# Body-Shield.net
KiCad netlist of a schematic drawn in EAGLE
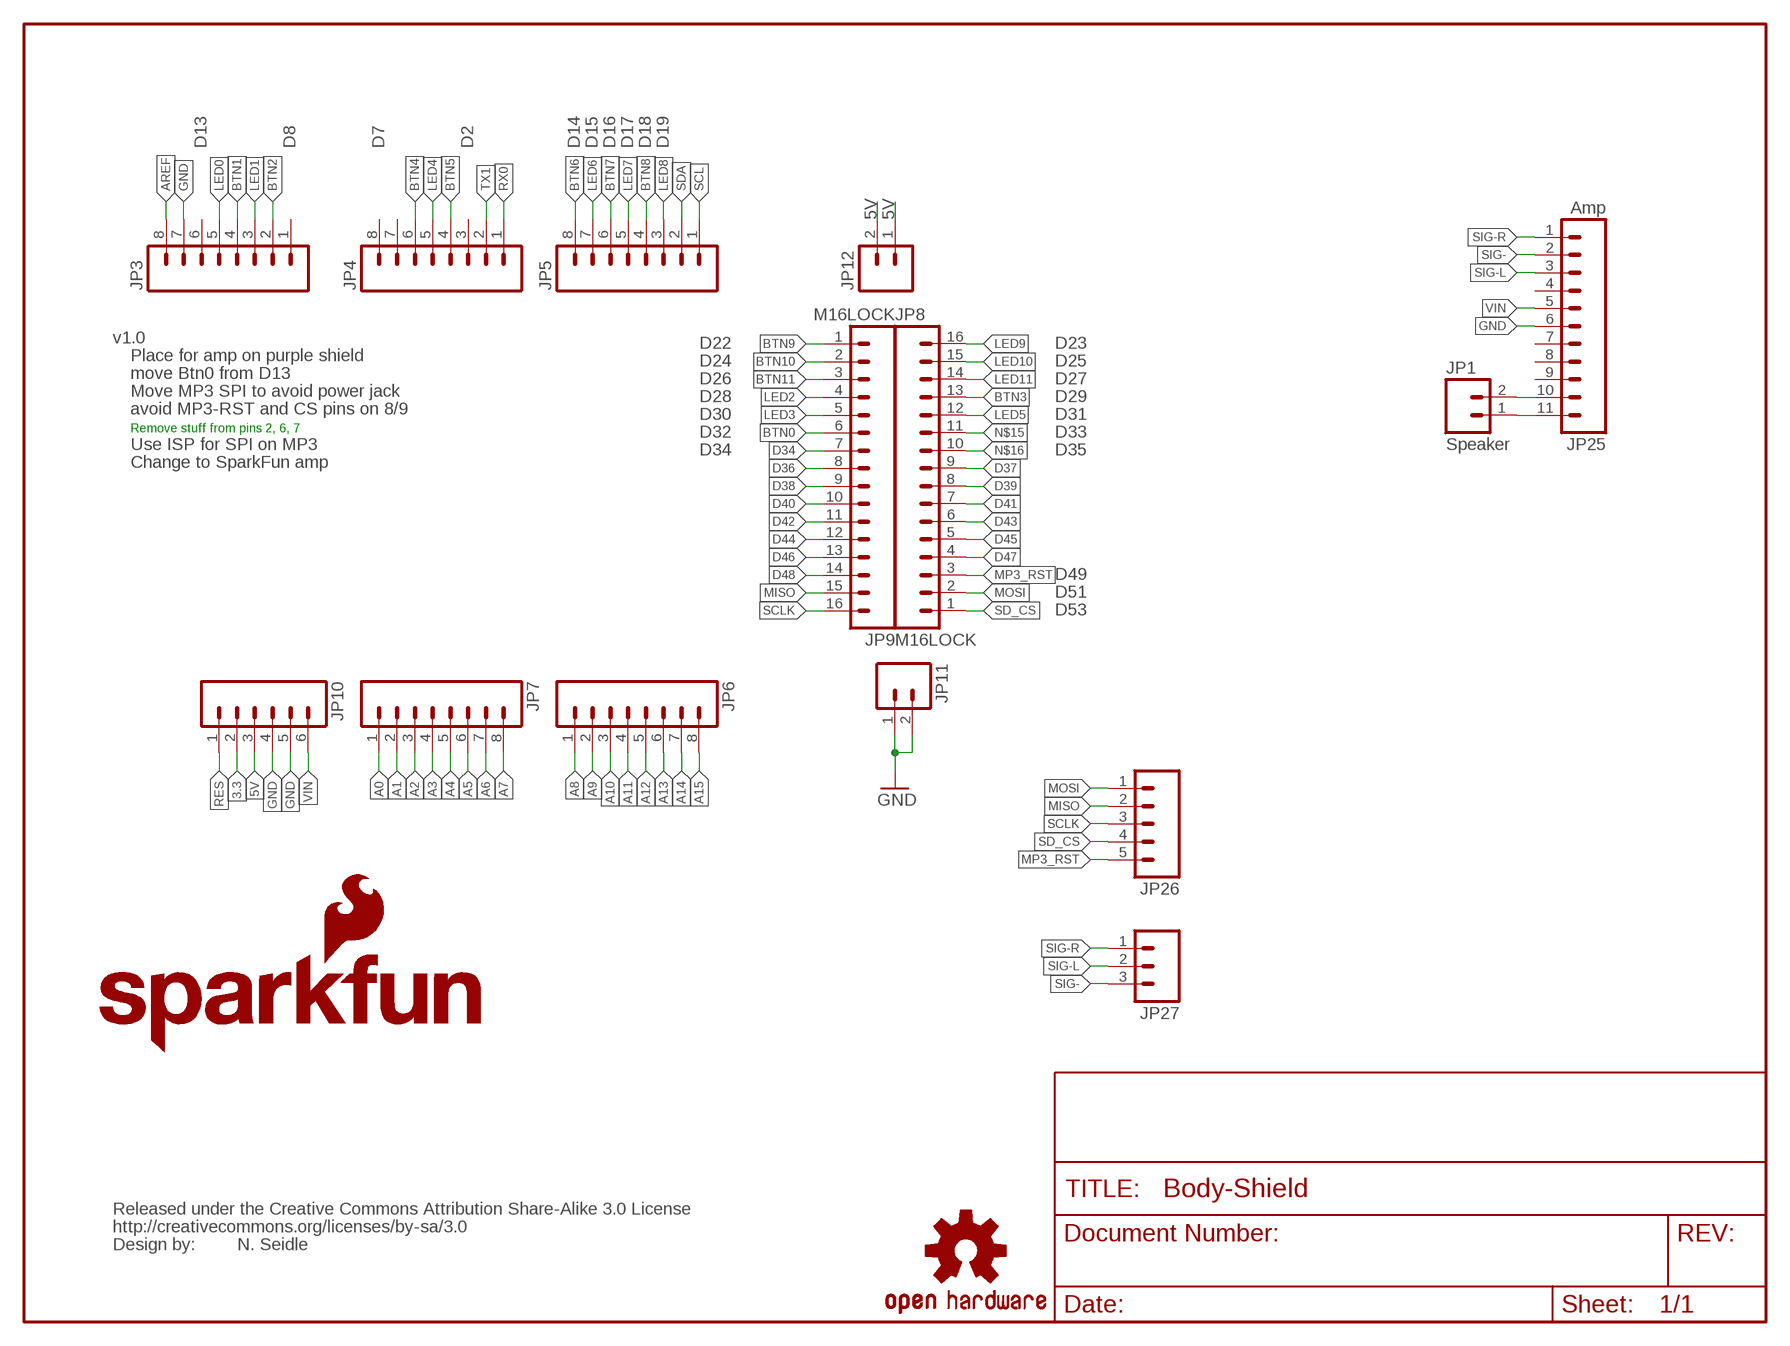
[diagram p0: schematic, sheet 1, part 1 of 2]
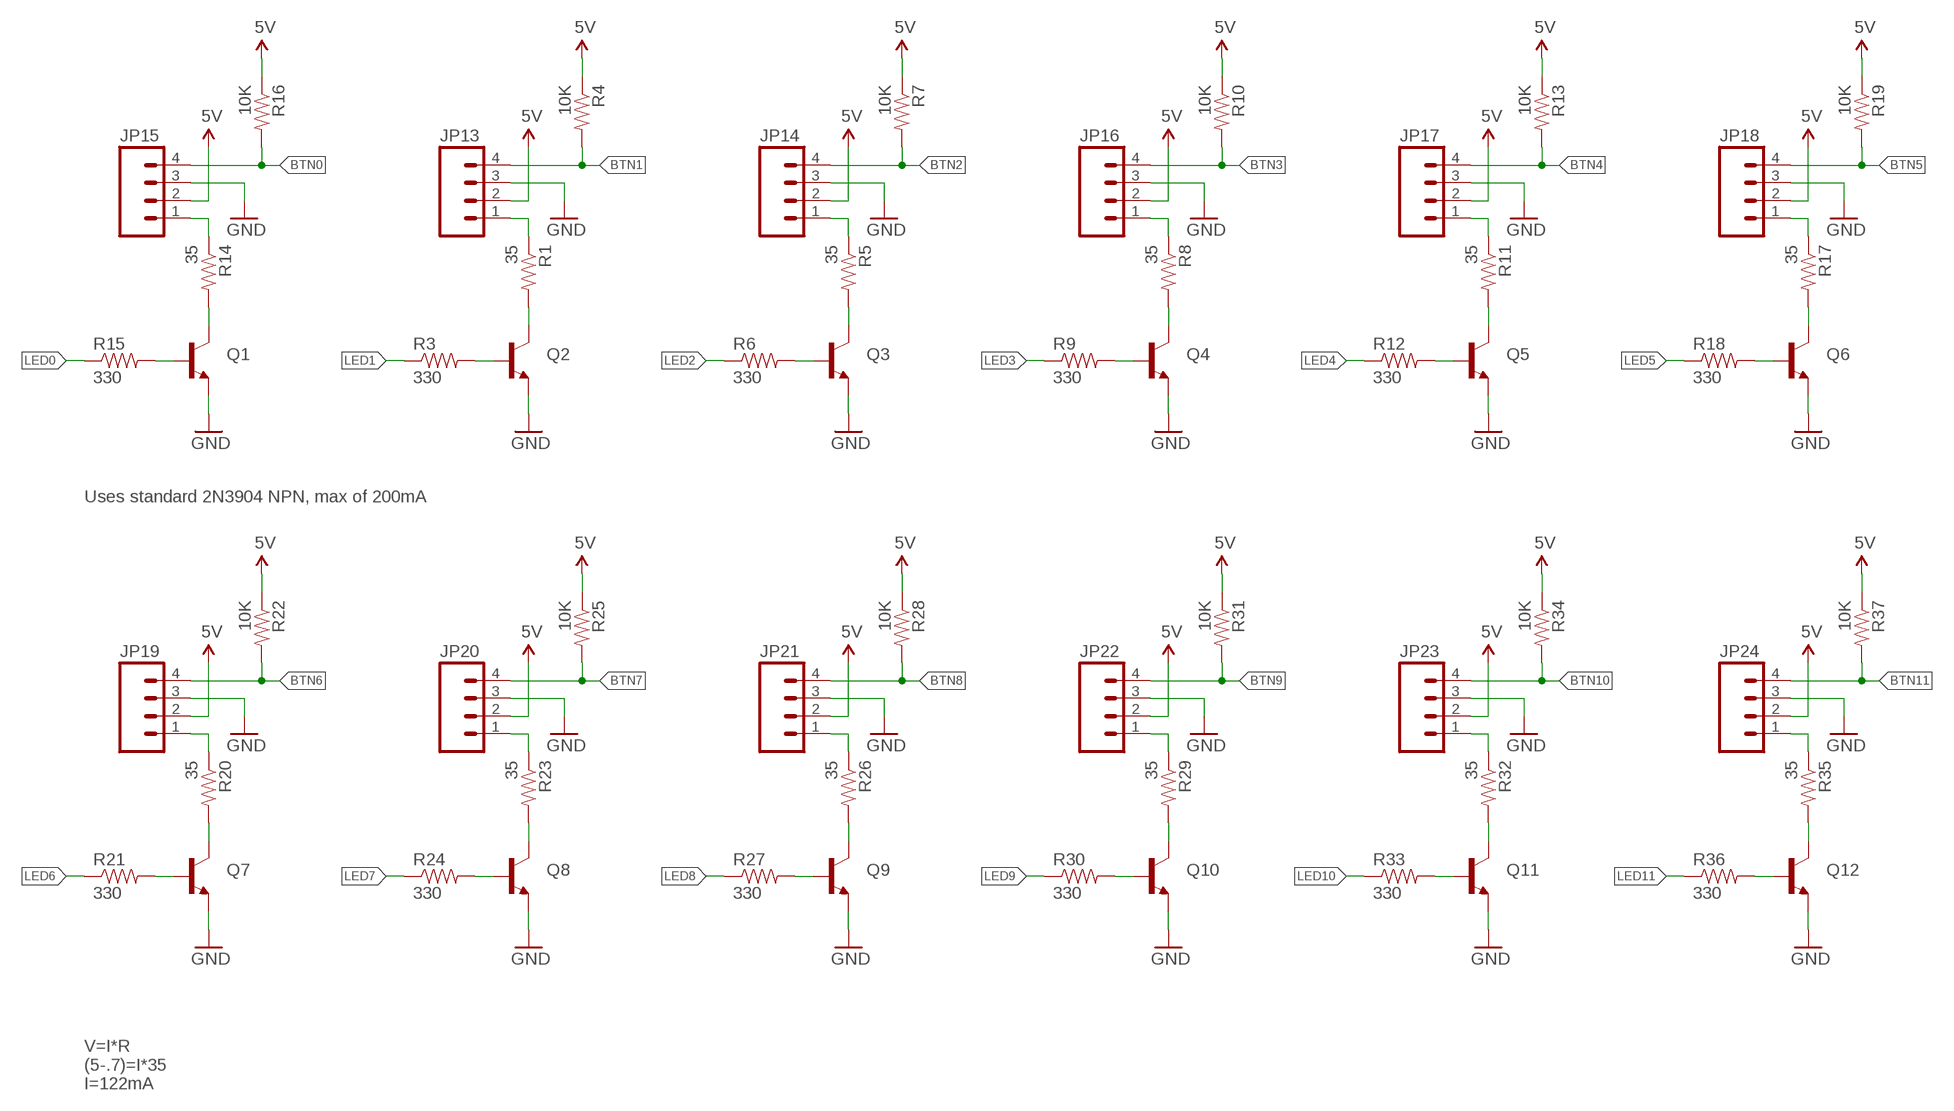
[diagram p1: schematic, sheet 1, part 2 of 2]

(export (version "E")
  (design (tool "Eeschema 10.0.6"))
  (components
    (comp (ref "JP1")
      (value "Speaker")
      (footprint "eagle-import:JST-2-PTH-VERT")
      (libsource (lib "eagle-import") (part "M02JST-PTH-VERT"))
    )
    (comp (ref "JP3")
      (value "M08LOCK")
      (footprint "eagle-import:1X08_LOCK")
      (libsource (lib "eagle-import") (part "M08LOCK"))
    )
    (comp (ref "JP4")
      (value "M08LOCK")
      (footprint "eagle-import:1X08_LOCK")
      (libsource (lib "eagle-import") (part "M08LOCK"))
    )
    (comp (ref "JP5")
      (value "M08LOCK")
      (footprint "eagle-import:1X08_LOCK")
      (libsource (lib "eagle-import") (part "M08LOCK"))
    )
    (comp (ref "JP6")
      (value "M08LOCK")
      (footprint "eagle-import:1X08_LOCK")
      (libsource (lib "eagle-import") (part "M08LOCK"))
    )
    (comp (ref "JP7")
      (value "M08LOCK")
      (footprint "eagle-import:1X08_LOCK")
      (libsource (lib "eagle-import") (part "M08LOCK"))
    )
    (comp (ref "JP8")
      (value "M16LOCK")
      (footprint "eagle-import:1X16_LOCK")
      (libsource (lib "eagle-import") (part "M16LOCK"))
    )
    (comp (ref "JP9")
      (value "M16LOCK")
      (footprint "eagle-import:1X16_LOCK")
      (libsource (lib "eagle-import") (part "M16LOCK"))
    )
    (comp (ref "JP10")
      (value "M06LOCK")
      (footprint "eagle-import:1X06_LOCK")
      (libsource (lib "eagle-import") (part "M06LOCK"))
    )
    (comp (ref "JP11")
      (value "M02LOCK")
      (footprint "eagle-import:1X02_LOCK")
      (libsource (lib "eagle-import") (part "M02LOCK"))
    )
    (comp (ref "JP12")
      (value "M02LOCK")
      (footprint "eagle-import:1X02_LOCK")
      (libsource (lib "eagle-import") (part "M02LOCK"))
    )
    (comp (ref "JP13")
      (value "M04JST-PTH-VERT")
      (footprint "eagle-import:JST-4-PTH-VERT")
      (libsource (lib "eagle-import") (part "M04JST-PTH-VERT"))
    )
    (comp (ref "JP14")
      (value "M04JST-PTH-VERT")
      (footprint "eagle-import:JST-4-PTH-VERT")
      (libsource (lib "eagle-import") (part "M04JST-PTH-VERT"))
    )
    (comp (ref "JP15")
      (value "M04JST-PTH-VERT")
      (footprint "eagle-import:JST-4-PTH-VERT")
      (libsource (lib "eagle-import") (part "M04JST-PTH-VERT"))
    )
    (comp (ref "JP16")
      (value "M04JST-PTH-VERT")
      (footprint "eagle-import:JST-4-PTH-VERT")
      (libsource (lib "eagle-import") (part "M04JST-PTH-VERT"))
    )
    (comp (ref "JP17")
      (value "M04JST-PTH-VERT")
      (footprint "eagle-import:JST-4-PTH-VERT")
      (libsource (lib "eagle-import") (part "M04JST-PTH-VERT"))
    )
    (comp (ref "JP18")
      (value "M04JST-PTH-VERT")
      (footprint "eagle-import:JST-4-PTH-VERT")
      (libsource (lib "eagle-import") (part "M04JST-PTH-VERT"))
    )
    (comp (ref "JP19")
      (value "M04JST-PTH-VERT")
      (footprint "eagle-import:JST-4-PTH-VERT")
      (libsource (lib "eagle-import") (part "M04JST-PTH-VERT"))
    )
    (comp (ref "JP20")
      (value "M04JST-PTH-VERT")
      (footprint "eagle-import:JST-4-PTH-VERT")
      (libsource (lib "eagle-import") (part "M04JST-PTH-VERT"))
    )
    (comp (ref "JP21")
      (value "M04JST-PTH-VERT")
      (footprint "eagle-import:JST-4-PTH-VERT")
      (libsource (lib "eagle-import") (part "M04JST-PTH-VERT"))
    )
    (comp (ref "JP22")
      (value "M04JST-PTH-VERT")
      (footprint "eagle-import:JST-4-PTH-VERT")
      (libsource (lib "eagle-import") (part "M04JST-PTH-VERT"))
    )
    (comp (ref "JP23")
      (value "M04JST-PTH-VERT")
      (footprint "eagle-import:JST-4-PTH-VERT")
      (libsource (lib "eagle-import") (part "M04JST-PTH-VERT"))
    )
    (comp (ref "JP24")
      (value "M04JST-PTH-VERT")
      (footprint "eagle-import:JST-4-PTH-VERT")
      (libsource (lib "eagle-import") (part "M04JST-PTH-VERT"))
    )
    (comp (ref "JP25")
      (value "Amp")
      (footprint "eagle-import:1X11")
      (libsource (lib "eagle-import") (part "M11PTH"))
    )
    (comp (ref "JP26")
      (value "M05JST")
      (footprint "eagle-import:JST-5-PTH")
      (libsource (lib "eagle-import") (part "M05JST"))
    )
    (comp (ref "JP27")
      (value "M03JST-PTH")
      (footprint "eagle-import:JST-3-PTH")
      (libsource (lib "eagle-import") (part "M03JST-PTH"))
    )
    (comp (ref "LOGO1")
      (value "SFE_LOGO_NAME_FLAME.1_INCH")
      (footprint "eagle-import:SFE_LOGO_NAME_FLAME_.1")
      (libsource (lib "eagle-import") (part "SFE_LOGO_NAME_FLAME.1_INCH"))
    )
    (comp (ref "LOGO2")
      (value "OSHW-LOGOS")
      (footprint "eagle-import:OSHW-LOGO-S")
      (libsource (lib "eagle-import") (part "OSHW-LOGOS"))
    )
    (comp (ref "Q1")
      (value "TRANSISTOR_NPN2N3904")
      (footprint "eagle-import:TO-92")
      (libsource (lib "eagle-import") (part "TRANSISTOR_NPN2N3904"))
    )
    (comp (ref "Q2")
      (value "TRANSISTOR_NPN2N3904")
      (footprint "eagle-import:TO-92")
      (libsource (lib "eagle-import") (part "TRANSISTOR_NPN2N3904"))
    )
    (comp (ref "Q3")
      (value "TRANSISTOR_NPN2N3904")
      (footprint "eagle-import:TO-92")
      (libsource (lib "eagle-import") (part "TRANSISTOR_NPN2N3904"))
    )
    (comp (ref "Q4")
      (value "TRANSISTOR_NPN2N3904")
      (footprint "eagle-import:TO-92")
      (libsource (lib "eagle-import") (part "TRANSISTOR_NPN2N3904"))
    )
    (comp (ref "Q5")
      (value "TRANSISTOR_NPN2N3904")
      (footprint "eagle-import:TO-92")
      (libsource (lib "eagle-import") (part "TRANSISTOR_NPN2N3904"))
    )
    (comp (ref "Q6")
      (value "TRANSISTOR_NPN2N3904")
      (footprint "eagle-import:TO-92")
      (libsource (lib "eagle-import") (part "TRANSISTOR_NPN2N3904"))
    )
    (comp (ref "Q7")
      (value "TRANSISTOR_NPN2N3904")
      (footprint "eagle-import:TO-92")
      (libsource (lib "eagle-import") (part "TRANSISTOR_NPN2N3904"))
    )
    (comp (ref "Q8")
      (value "TRANSISTOR_NPN2N3904")
      (footprint "eagle-import:TO-92")
      (libsource (lib "eagle-import") (part "TRANSISTOR_NPN2N3904"))
    )
    (comp (ref "Q9")
      (value "TRANSISTOR_NPN2N3904")
      (footprint "eagle-import:TO-92")
      (libsource (lib "eagle-import") (part "TRANSISTOR_NPN2N3904"))
    )
    (comp (ref "Q10")
      (value "TRANSISTOR_NPN2N3904")
      (footprint "eagle-import:TO-92")
      (libsource (lib "eagle-import") (part "TRANSISTOR_NPN2N3904"))
    )
    (comp (ref "Q11")
      (value "TRANSISTOR_NPN2N3904")
      (footprint "eagle-import:TO-92")
      (libsource (lib "eagle-import") (part "TRANSISTOR_NPN2N3904"))
    )
    (comp (ref "Q12")
      (value "TRANSISTOR_NPN2N3904")
      (footprint "eagle-import:TO-92")
      (libsource (lib "eagle-import") (part "TRANSISTOR_NPN2N3904"))
    )
    (comp (ref "R1")
      (value "35")
      (footprint "eagle-import:AXIAL-0.3")
      (libsource (lib "eagle-import") (part "RESISTORPTH1"))
    )
    (comp (ref "R3")
      (value "330")
      (footprint "eagle-import:AXIAL-0.3")
      (libsource (lib "eagle-import") (part "RESISTORPTH1"))
    )
    (comp (ref "R4")
      (value "10K")
      (footprint "eagle-import:AXIAL-0.3")
      (libsource (lib "eagle-import") (part "RESISTORPTH1"))
    )
    (comp (ref "R5")
      (value "35")
      (footprint "eagle-import:AXIAL-0.3")
      (libsource (lib "eagle-import") (part "RESISTORPTH1"))
    )
    (comp (ref "R6")
      (value "330")
      (footprint "eagle-import:AXIAL-0.3")
      (libsource (lib "eagle-import") (part "RESISTORPTH1"))
    )
    (comp (ref "R7")
      (value "10K")
      (footprint "eagle-import:AXIAL-0.3")
      (libsource (lib "eagle-import") (part "RESISTORPTH1"))
    )
    (comp (ref "R8")
      (value "35")
      (footprint "eagle-import:AXIAL-0.3")
      (libsource (lib "eagle-import") (part "RESISTORPTH1"))
    )
    (comp (ref "R9")
      (value "330")
      (footprint "eagle-import:AXIAL-0.3")
      (libsource (lib "eagle-import") (part "RESISTORPTH1"))
    )
    (comp (ref "R10")
      (value "10K")
      (footprint "eagle-import:AXIAL-0.3")
      (libsource (lib "eagle-import") (part "RESISTORPTH1"))
    )
    (comp (ref "R11")
      (value "35")
      (footprint "eagle-import:AXIAL-0.3")
      (libsource (lib "eagle-import") (part "RESISTORPTH1"))
    )
    (comp (ref "R12")
      (value "330")
      (footprint "eagle-import:AXIAL-0.3")
      (libsource (lib "eagle-import") (part "RESISTORPTH1"))
    )
    (comp (ref "R13")
      (value "10K")
      (footprint "eagle-import:AXIAL-0.3")
      (libsource (lib "eagle-import") (part "RESISTORPTH1"))
    )
    (comp (ref "R14")
      (value "35")
      (footprint "eagle-import:AXIAL-0.3")
      (libsource (lib "eagle-import") (part "RESISTORPTH1"))
    )
    (comp (ref "R15")
      (value "330")
      (footprint "eagle-import:AXIAL-0.3")
      (libsource (lib "eagle-import") (part "RESISTORPTH1"))
    )
    (comp (ref "R16")
      (value "10K")
      (footprint "eagle-import:AXIAL-0.3")
      (libsource (lib "eagle-import") (part "RESISTORPTH1"))
    )
    (comp (ref "R17")
      (value "35")
      (footprint "eagle-import:AXIAL-0.3")
      (libsource (lib "eagle-import") (part "RESISTORPTH1"))
    )
    (comp (ref "R18")
      (value "330")
      (footprint "eagle-import:AXIAL-0.3")
      (libsource (lib "eagle-import") (part "RESISTORPTH1"))
    )
    (comp (ref "R19")
      (value "10K")
      (footprint "eagle-import:AXIAL-0.3")
      (libsource (lib "eagle-import") (part "RESISTORPTH1"))
    )
    (comp (ref "R20")
      (value "35")
      (footprint "eagle-import:AXIAL-0.3")
      (libsource (lib "eagle-import") (part "RESISTORPTH1"))
    )
    (comp (ref "R21")
      (value "330")
      (footprint "eagle-import:AXIAL-0.3")
      (libsource (lib "eagle-import") (part "RESISTORPTH1"))
    )
    (comp (ref "R22")
      (value "10K")
      (footprint "eagle-import:AXIAL-0.3")
      (libsource (lib "eagle-import") (part "RESISTORPTH1"))
    )
    (comp (ref "R23")
      (value "35")
      (footprint "eagle-import:AXIAL-0.3")
      (libsource (lib "eagle-import") (part "RESISTORPTH1"))
    )
    (comp (ref "R24")
      (value "330")
      (footprint "eagle-import:AXIAL-0.3")
      (libsource (lib "eagle-import") (part "RESISTORPTH1"))
    )
    (comp (ref "R25")
      (value "10K")
      (footprint "eagle-import:AXIAL-0.3")
      (libsource (lib "eagle-import") (part "RESISTORPTH1"))
    )
    (comp (ref "R26")
      (value "35")
      (footprint "eagle-import:AXIAL-0.3")
      (libsource (lib "eagle-import") (part "RESISTORPTH1"))
    )
    (comp (ref "R27")
      (value "330")
      (footprint "eagle-import:AXIAL-0.3")
      (libsource (lib "eagle-import") (part "RESISTORPTH1"))
    )
    (comp (ref "R28")
      (value "10K")
      (footprint "eagle-import:AXIAL-0.3")
      (libsource (lib "eagle-import") (part "RESISTORPTH1"))
    )
    (comp (ref "R29")
      (value "35")
      (footprint "eagle-import:AXIAL-0.3")
      (libsource (lib "eagle-import") (part "RESISTORPTH1"))
    )
    (comp (ref "R30")
      (value "330")
      (footprint "eagle-import:AXIAL-0.3")
      (libsource (lib "eagle-import") (part "RESISTORPTH1"))
    )
    (comp (ref "R31")
      (value "10K")
      (footprint "eagle-import:AXIAL-0.3")
      (libsource (lib "eagle-import") (part "RESISTORPTH1"))
    )
    (comp (ref "R32")
      (value "35")
      (footprint "eagle-import:AXIAL-0.3")
      (libsource (lib "eagle-import") (part "RESISTORPTH1"))
    )
    (comp (ref "R33")
      (value "330")
      (footprint "eagle-import:AXIAL-0.3")
      (libsource (lib "eagle-import") (part "RESISTORPTH1"))
    )
    (comp (ref "R34")
      (value "10K")
      (footprint "eagle-import:AXIAL-0.3")
      (libsource (lib "eagle-import") (part "RESISTORPTH1"))
    )
    (comp (ref "R35")
      (value "35")
      (footprint "eagle-import:AXIAL-0.3")
      (libsource (lib "eagle-import") (part "RESISTORPTH1"))
    )
    (comp (ref "R36")
      (value "330")
      (footprint "eagle-import:AXIAL-0.3")
      (libsource (lib "eagle-import") (part "RESISTORPTH1"))
    )
    (comp (ref "R37")
      (value "10K")
      (footprint "eagle-import:AXIAL-0.3")
      (libsource (lib "eagle-import") (part "RESISTORPTH1"))
    )
    (comp (ref "U$2")
      (value "CREATIVE_COMMONS")
      (footprint "eagle-import:CREATIVE_COMMONS")
      (libsource (lib "eagle-import") (part "CREATIVE_COMMONS"))
    )
  )
  (nets
    (net (code "1") (name "3.3") (class "Default")
      (node (ref "JP10") (pin "2") (pinfunction "2_2") (pintype "passive"))
    )
    (net (code "2") (name "5V") (class "Default")
      (node (ref "JP10") (pin "3") (pinfunction "3_3") (pintype "passive"))
      (node (ref "JP12") (pin "1") (pinfunction "1_1") (pintype "passive"))
      (node (ref "JP12") (pin "2") (pinfunction "2_2") (pintype "passive"))
      (node (ref "JP13") (pin "2") (pinfunction "2_2") (pintype "passive"))
      (node (ref "JP14") (pin "2") (pinfunction "2_2") (pintype "passive"))
      (node (ref "JP15") (pin "2") (pinfunction "2_2") (pintype "passive"))
      (node (ref "JP16") (pin "2") (pinfunction "2_2") (pintype "passive"))
      (node (ref "JP17") (pin "2") (pinfunction "2_2") (pintype "passive"))
      (node (ref "JP18") (pin "2") (pinfunction "2_2") (pintype "passive"))
      (node (ref "JP19") (pin "2") (pinfunction "2_2") (pintype "passive"))
      (node (ref "JP20") (pin "2") (pinfunction "2_2") (pintype "passive"))
      (node (ref "JP21") (pin "2") (pinfunction "2_2") (pintype "passive"))
      (node (ref "JP22") (pin "2") (pinfunction "2_2") (pintype "passive"))
      (node (ref "JP23") (pin "2") (pinfunction "2_2") (pintype "passive"))
      (node (ref "JP24") (pin "2") (pinfunction "2_2") (pintype "passive"))
      (node (ref "R10") (pin "P$1") (pinfunction "1_P$1") (pintype "passive"))
      (node (ref "R13") (pin "P$1") (pinfunction "1_P$1") (pintype "passive"))
      (node (ref "R16") (pin "P$1") (pinfunction "1_P$1") (pintype "passive"))
      (node (ref "R19") (pin "P$1") (pinfunction "1_P$1") (pintype "passive"))
      (node (ref "R22") (pin "P$1") (pinfunction "1_P$1") (pintype "passive"))
      (node (ref "R25") (pin "P$1") (pinfunction "1_P$1") (pintype "passive"))
      (node (ref "R28") (pin "P$1") (pinfunction "1_P$1") (pintype "passive"))
      (node (ref "R31") (pin "P$1") (pinfunction "1_P$1") (pintype "passive"))
      (node (ref "R34") (pin "P$1") (pinfunction "1_P$1") (pintype "passive"))
      (node (ref "R37") (pin "P$1") (pinfunction "1_P$1") (pintype "passive"))
      (node (ref "R4") (pin "P$1") (pinfunction "1_P$1") (pintype "passive"))
      (node (ref "R7") (pin "P$1") (pinfunction "1_P$1") (pintype "passive"))
    )
    (net (code "3") (name "A0") (class "Default")
      (node (ref "JP7") (pin "1") (pinfunction "1_1") (pintype "passive"))
    )
    (net (code "4") (name "A1") (class "Default")
      (node (ref "JP7") (pin "2") (pinfunction "2_2") (pintype "passive"))
    )
    (net (code "5") (name "A2") (class "Default")
      (node (ref "JP7") (pin "3") (pinfunction "3_3") (pintype "passive"))
    )
    (net (code "6") (name "A3") (class "Default")
      (node (ref "JP7") (pin "4") (pinfunction "4_4") (pintype "passive"))
    )
    (net (code "7") (name "A4") (class "Default")
      (node (ref "JP7") (pin "5") (pinfunction "5_5") (pintype "passive"))
    )
    (net (code "8") (name "A5") (class "Default")
      (node (ref "JP7") (pin "6") (pinfunction "6_6") (pintype "passive"))
    )
    (net (code "9") (name "A6") (class "Default")
      (node (ref "JP7") (pin "7") (pinfunction "7_7") (pintype "passive"))
    )
    (net (code "10") (name "A7") (class "Default")
      (node (ref "JP7") (pin "8") (pinfunction "8_8") (pintype "passive"))
    )
    (net (code "11") (name "A8") (class "Default")
      (node (ref "JP6") (pin "1") (pinfunction "1_1") (pintype "passive"))
    )
    (net (code "12") (name "A9") (class "Default")
      (node (ref "JP6") (pin "2") (pinfunction "2_2") (pintype "passive"))
    )
    (net (code "13") (name "A10") (class "Default")
      (node (ref "JP6") (pin "3") (pinfunction "3_3") (pintype "passive"))
    )
    (net (code "14") (name "A11") (class "Default")
      (node (ref "JP6") (pin "4") (pinfunction "4_4") (pintype "passive"))
    )
    (net (code "15") (name "A12") (class "Default")
      (node (ref "JP6") (pin "5") (pinfunction "5_5") (pintype "passive"))
    )
    (net (code "16") (name "A13") (class "Default")
      (node (ref "JP6") (pin "6") (pinfunction "6_6") (pintype "passive"))
    )
    (net (code "17") (name "A14") (class "Default")
      (node (ref "JP6") (pin "7") (pinfunction "7_7") (pintype "passive"))
    )
    (net (code "18") (name "A15") (class "Default")
      (node (ref "JP6") (pin "8") (pinfunction "8_8") (pintype "passive"))
    )
    (net (code "19") (name "AREF") (class "Default")
      (node (ref "JP3") (pin "8") (pinfunction "8_8") (pintype "passive"))
    )
    (net (code "20") (name "BTN0") (class "Default")
      (node (ref "JP15") (pin "4") (pinfunction "4_4") (pintype "passive"))
      (node (ref "JP9") (pin "6") (pinfunction "6_6") (pintype "passive"))
      (node (ref "R16") (pin "P$2") (pinfunction "2_P$2") (pintype "passive"))
    )
    (net (code "21") (name "BTN1") (class "Default")
      (node (ref "JP13") (pin "4") (pinfunction "4_4") (pintype "passive"))
      (node (ref "JP3") (pin "4") (pinfunction "4_4") (pintype "passive"))
      (node (ref "R4") (pin "P$2") (pinfunction "2_P$2") (pintype "passive"))
    )
    (net (code "22") (name "BTN2") (class "Default")
      (node (ref "JP14") (pin "4") (pinfunction "4_4") (pintype "passive"))
      (node (ref "JP3") (pin "2") (pinfunction "2_2") (pintype "passive"))
      (node (ref "R7") (pin "P$2") (pinfunction "2_P$2") (pintype "passive"))
    )
    (net (code "23") (name "BTN3") (class "Default")
      (node (ref "JP16") (pin "4") (pinfunction "4_4") (pintype "passive"))
      (node (ref "JP8") (pin "13") (pinfunction "13_13") (pintype "passive"))
      (node (ref "R10") (pin "P$2") (pinfunction "2_P$2") (pintype "passive"))
    )
    (net (code "24") (name "BTN4") (class "Default")
      (node (ref "JP17") (pin "4") (pinfunction "4_4") (pintype "passive"))
      (node (ref "JP4") (pin "6") (pinfunction "6_6") (pintype "passive"))
      (node (ref "R13") (pin "P$2") (pinfunction "2_P$2") (pintype "passive"))
    )
    (net (code "25") (name "BTN5") (class "Default")
      (node (ref "JP18") (pin "4") (pinfunction "4_4") (pintype "passive"))
      (node (ref "JP4") (pin "4") (pinfunction "4_4") (pintype "passive"))
      (node (ref "R19") (pin "P$2") (pinfunction "2_P$2") (pintype "passive"))
    )
    (net (code "26") (name "BTN6") (class "Default")
      (node (ref "JP19") (pin "4") (pinfunction "4_4") (pintype "passive"))
      (node (ref "JP5") (pin "8") (pinfunction "8_8") (pintype "passive"))
      (node (ref "R22") (pin "P$2") (pinfunction "2_P$2") (pintype "passive"))
    )
    (net (code "27") (name "BTN7") (class "Default")
      (node (ref "JP20") (pin "4") (pinfunction "4_4") (pintype "passive"))
      (node (ref "JP5") (pin "6") (pinfunction "6_6") (pintype "passive"))
      (node (ref "R25") (pin "P$2") (pinfunction "2_P$2") (pintype "passive"))
    )
    (net (code "28") (name "BTN8") (class "Default")
      (node (ref "JP21") (pin "4") (pinfunction "4_4") (pintype "passive"))
      (node (ref "JP5") (pin "4") (pinfunction "4_4") (pintype "passive"))
      (node (ref "R28") (pin "P$2") (pinfunction "2_P$2") (pintype "passive"))
    )
    (net (code "29") (name "BTN9") (class "Default")
      (node (ref "JP22") (pin "4") (pinfunction "4_4") (pintype "passive"))
      (node (ref "JP9") (pin "1") (pinfunction "1_1") (pintype "passive"))
      (node (ref "R31") (pin "P$2") (pinfunction "2_P$2") (pintype "passive"))
    )
    (net (code "30") (name "BTN10") (class "Default")
      (node (ref "JP23") (pin "4") (pinfunction "4_4") (pintype "passive"))
      (node (ref "JP9") (pin "2") (pinfunction "2_2") (pintype "passive"))
      (node (ref "R34") (pin "P$2") (pinfunction "2_P$2") (pintype "passive"))
    )
    (net (code "31") (name "BTN11") (class "Default")
      (node (ref "JP24") (pin "4") (pinfunction "4_4") (pintype "passive"))
      (node (ref "JP9") (pin "3") (pinfunction "3_3") (pintype "passive"))
      (node (ref "R37") (pin "P$2") (pinfunction "2_P$2") (pintype "passive"))
    )
    (net (code "32") (name "D34") (class "Default")
      (node (ref "JP9") (pin "7") (pinfunction "7_7") (pintype "passive"))
    )
    (net (code "33") (name "D36") (class "Default")
      (node (ref "JP9") (pin "8") (pinfunction "8_8") (pintype "passive"))
    )
    (net (code "34") (name "D37") (class "Default")
      (node (ref "JP8") (pin "9") (pinfunction "9_9") (pintype "passive"))
    )
    (net (code "35") (name "D38") (class "Default")
      (node (ref "JP9") (pin "9") (pinfunction "9_9") (pintype "passive"))
    )
    (net (code "36") (name "D39") (class "Default")
      (node (ref "JP8") (pin "8") (pinfunction "8_8") (pintype "passive"))
    )
    (net (code "37") (name "D40") (class "Default")
      (node (ref "JP9") (pin "10") (pinfunction "10_10") (pintype "passive"))
    )
    (net (code "38") (name "D41") (class "Default")
      (node (ref "JP8") (pin "7") (pinfunction "7_7") (pintype "passive"))
    )
    (net (code "39") (name "D42") (class "Default")
      (node (ref "JP9") (pin "11") (pinfunction "11_11") (pintype "passive"))
    )
    (net (code "40") (name "D43") (class "Default")
      (node (ref "JP8") (pin "6") (pinfunction "6_6") (pintype "passive"))
    )
    (net (code "41") (name "D44") (class "Default")
      (node (ref "JP9") (pin "12") (pinfunction "12_12") (pintype "passive"))
    )
    (net (code "42") (name "D45") (class "Default")
      (node (ref "JP8") (pin "5") (pinfunction "5_5") (pintype "passive"))
    )
    (net (code "43") (name "D46") (class "Default")
      (node (ref "JP9") (pin "13") (pinfunction "13_13") (pintype "passive"))
    )
    (net (code "44") (name "D47") (class "Default")
      (node (ref "JP8") (pin "4") (pinfunction "4_4") (pintype "passive"))
    )
    (net (code "45") (name "D48") (class "Default")
      (node (ref "JP9") (pin "14") (pinfunction "14_14") (pintype "passive"))
    )
    (net (code "46") (name "GND") (class "Default")
      (node (ref "JP10") (pin "4") (pinfunction "4_4") (pintype "passive"))
      (node (ref "JP10") (pin "5") (pinfunction "5_5") (pintype "passive"))
      (node (ref "JP11") (pin "1") (pinfunction "1_1") (pintype "passive"))
      (node (ref "JP11") (pin "2") (pinfunction "2_2") (pintype "passive"))
      (node (ref "JP13") (pin "3") (pinfunction "3_3") (pintype "passive"))
      (node (ref "JP14") (pin "3") (pinfunction "3_3") (pintype "passive"))
      (node (ref "JP15") (pin "3") (pinfunction "3_3") (pintype "passive"))
      (node (ref "JP16") (pin "3") (pinfunction "3_3") (pintype "passive"))
      (node (ref "JP17") (pin "3") (pinfunction "3_3") (pintype "passive"))
      (node (ref "JP18") (pin "3") (pinfunction "3_3") (pintype "passive"))
      (node (ref "JP19") (pin "3") (pinfunction "3_3") (pintype "passive"))
      (node (ref "JP20") (pin "3") (pinfunction "3_3") (pintype "passive"))
      (node (ref "JP21") (pin "3") (pinfunction "3_3") (pintype "passive"))
      (node (ref "JP22") (pin "3") (pinfunction "3_3") (pintype "passive"))
      (node (ref "JP23") (pin "3") (pinfunction "3_3") (pintype "passive"))
      (node (ref "JP24") (pin "3") (pinfunction "3_3") (pintype "passive"))
      (node (ref "JP25") (pin "6") (pinfunction "6_6") (pintype "passive"))
      (node (ref "JP3") (pin "7") (pinfunction "7_7") (pintype "passive"))
      (node (ref "Q1") (pin "1") (pinfunction "E_1") (pintype "passive"))
      (node (ref "Q10") (pin "1") (pinfunction "E_1") (pintype "passive"))
      (node (ref "Q11") (pin "1") (pinfunction "E_1") (pintype "passive"))
      (node (ref "Q12") (pin "1") (pinfunction "E_1") (pintype "passive"))
      (node (ref "Q2") (pin "1") (pinfunction "E_1") (pintype "passive"))
      (node (ref "Q3") (pin "1") (pinfunction "E_1") (pintype "passive"))
      (node (ref "Q4") (pin "1") (pinfunction "E_1") (pintype "passive"))
      (node (ref "Q5") (pin "1") (pinfunction "E_1") (pintype "passive"))
      (node (ref "Q6") (pin "1") (pinfunction "E_1") (pintype "passive"))
      (node (ref "Q7") (pin "1") (pinfunction "E_1") (pintype "passive"))
      (node (ref "Q8") (pin "1") (pinfunction "E_1") (pintype "passive"))
      (node (ref "Q9") (pin "1") (pinfunction "E_1") (pintype "passive"))
    )
    (net (code "47") (name "LED0") (class "Default")
      (node (ref "JP3") (pin "5") (pinfunction "5_5") (pintype "passive"))
      (node (ref "R15") (pin "P$1") (pinfunction "1_P$1") (pintype "passive"))
    )
    (net (code "48") (name "LED1") (class "Default")
      (node (ref "JP3") (pin "3") (pinfunction "3_3") (pintype "passive"))
      (node (ref "R3") (pin "P$1") (pinfunction "1_P$1") (pintype "passive"))
    )
    (net (code "49") (name "LED2") (class "Default")
      (node (ref "JP9") (pin "4") (pinfunction "4_4") (pintype "passive"))
      (node (ref "R6") (pin "P$1") (pinfunction "1_P$1") (pintype "passive"))
    )
    (net (code "50") (name "LED3") (class "Default")
      (node (ref "JP9") (pin "5") (pinfunction "5_5") (pintype "passive"))
      (node (ref "R9") (pin "P$1") (pinfunction "1_P$1") (pintype "passive"))
    )
    (net (code "51") (name "LED4") (class "Default")
      (node (ref "JP4") (pin "5") (pinfunction "5_5") (pintype "passive"))
      (node (ref "R12") (pin "P$1") (pinfunction "1_P$1") (pintype "passive"))
    )
    (net (code "52") (name "LED5") (class "Default")
      (node (ref "JP8") (pin "12") (pinfunction "12_12") (pintype "passive"))
      (node (ref "R18") (pin "P$1") (pinfunction "1_P$1") (pintype "passive"))
    )
    (net (code "53") (name "LED6") (class "Default")
      (node (ref "JP5") (pin "7") (pinfunction "7_7") (pintype "passive"))
      (node (ref "R21") (pin "P$1") (pinfunction "1_P$1") (pintype "passive"))
    )
    (net (code "54") (name "LED7") (class "Default")
      (node (ref "JP5") (pin "5") (pinfunction "5_5") (pintype "passive"))
      (node (ref "R24") (pin "P$1") (pinfunction "1_P$1") (pintype "passive"))
    )
    (net (code "55") (name "LED8") (class "Default")
      (node (ref "JP5") (pin "3") (pinfunction "3_3") (pintype "passive"))
      (node (ref "R27") (pin "P$1") (pinfunction "1_P$1") (pintype "passive"))
    )
    (net (code "56") (name "LED9") (class "Default")
      (node (ref "JP8") (pin "16") (pinfunction "16_16") (pintype "passive"))
      (node (ref "R30") (pin "P$1") (pinfunction "1_P$1") (pintype "passive"))
    )
    (net (code "57") (name "LED10") (class "Default")
      (node (ref "JP8") (pin "15") (pinfunction "15_15") (pintype "passive"))
      (node (ref "R33") (pin "P$1") (pinfunction "1_P$1") (pintype "passive"))
    )
    (net (code "58") (name "LED11") (class "Default")
      (node (ref "JP8") (pin "14") (pinfunction "14_14") (pintype "passive"))
      (node (ref "R36") (pin "P$1") (pinfunction "1_P$1") (pintype "passive"))
    )
    (net (code "59") (name "MISO") (class "Default")
      (node (ref "JP26") (pin "2") (pinfunction "2_2") (pintype "passive"))
      (node (ref "JP9") (pin "15") (pinfunction "15_15") (pintype "passive"))
    )
    (net (code "60") (name "MOSI") (class "Default")
      (node (ref "JP26") (pin "1") (pinfunction "1_1") (pintype "passive"))
      (node (ref "JP8") (pin "2") (pinfunction "2_2") (pintype "passive"))
    )
    (net (code "61") (name "MP3_RST") (class "Default")
      (node (ref "JP26") (pin "5") (pinfunction "5_5") (pintype "passive"))
      (node (ref "JP8") (pin "3") (pinfunction "3_3") (pintype "passive"))
    )
    (net (code "62") (name "N$15") (class "Default")
      (node (ref "JP8") (pin "11") (pinfunction "11_11") (pintype "passive"))
    )
    (net (code "63") (name "N$16") (class "Default")
      (node (ref "JP8") (pin "10") (pinfunction "10_10") (pintype "passive"))
    )
    (net (code "64") (name "Net-(JP1-Pad1)") (class "Default")
      (node (ref "JP1") (pin "1") (pinfunction "1_1") (pintype "passive"))
      (node (ref "JP25") (pin "11") (pinfunction "11_11") (pintype "passive"))
    )
    (net (code "65") (name "Net-(JP1-Pad2)") (class "Default")
      (node (ref "JP1") (pin "2") (pinfunction "2_2") (pintype "passive"))
      (node (ref "JP25") (pin "10") (pinfunction "10_10") (pintype "passive"))
    )
    (net (code "66") (name "Net-(Q1-B)") (class "Default")
      (node (ref "Q1") (pin "2") (pinfunction "B_2") (pintype "passive"))
      (node (ref "R15") (pin "P$2") (pinfunction "2_P$2") (pintype "passive"))
    )
    (net (code "67") (name "Net-(Q1-C)") (class "Default")
      (node (ref "Q1") (pin "3") (pinfunction "C_3") (pintype "passive"))
      (node (ref "R14") (pin "P$2") (pinfunction "2_P$2") (pintype "passive"))
    )
    (net (code "68") (name "Net-(Q2-B)") (class "Default")
      (node (ref "Q2") (pin "2") (pinfunction "B_2") (pintype "passive"))
      (node (ref "R3") (pin "P$2") (pinfunction "2_P$2") (pintype "passive"))
    )
    (net (code "69") (name "Net-(Q2-C)") (class "Default")
      (node (ref "Q2") (pin "3") (pinfunction "C_3") (pintype "passive"))
      (node (ref "R1") (pin "P$2") (pinfunction "2_P$2") (pintype "passive"))
    )
    (net (code "70") (name "Net-(Q3-B)") (class "Default")
      (node (ref "Q3") (pin "2") (pinfunction "B_2") (pintype "passive"))
      (node (ref "R6") (pin "P$2") (pinfunction "2_P$2") (pintype "passive"))
    )
    (net (code "71") (name "Net-(Q3-C)") (class "Default")
      (node (ref "Q3") (pin "3") (pinfunction "C_3") (pintype "passive"))
      (node (ref "R5") (pin "P$2") (pinfunction "2_P$2") (pintype "passive"))
    )
    (net (code "72") (name "Net-(Q4-B)") (class "Default")
      (node (ref "Q4") (pin "2") (pinfunction "B_2") (pintype "passive"))
      (node (ref "R9") (pin "P$2") (pinfunction "2_P$2") (pintype "passive"))
    )
    (net (code "73") (name "Net-(Q4-C)") (class "Default")
      (node (ref "Q4") (pin "3") (pinfunction "C_3") (pintype "passive"))
      (node (ref "R8") (pin "P$2") (pinfunction "2_P$2") (pintype "passive"))
    )
    (net (code "74") (name "Net-(Q5-B)") (class "Default")
      (node (ref "Q5") (pin "2") (pinfunction "B_2") (pintype "passive"))
      (node (ref "R12") (pin "P$2") (pinfunction "2_P$2") (pintype "passive"))
    )
    (net (code "75") (name "Net-(Q5-C)") (class "Default")
      (node (ref "Q5") (pin "3") (pinfunction "C_3") (pintype "passive"))
      (node (ref "R11") (pin "P$2") (pinfunction "2_P$2") (pintype "passive"))
    )
    (net (code "76") (name "Net-(Q6-B)") (class "Default")
      (node (ref "Q6") (pin "2") (pinfunction "B_2") (pintype "passive"))
      (node (ref "R18") (pin "P$2") (pinfunction "2_P$2") (pintype "passive"))
    )
    (net (code "77") (name "Net-(Q6-C)") (class "Default")
      (node (ref "Q6") (pin "3") (pinfunction "C_3") (pintype "passive"))
      (node (ref "R17") (pin "P$2") (pinfunction "2_P$2") (pintype "passive"))
    )
    (net (code "78") (name "Net-(Q7-B)") (class "Default")
      (node (ref "Q7") (pin "2") (pinfunction "B_2") (pintype "passive"))
      (node (ref "R21") (pin "P$2") (pinfunction "2_P$2") (pintype "passive"))
    )
    (net (code "79") (name "Net-(Q7-C)") (class "Default")
      (node (ref "Q7") (pin "3") (pinfunction "C_3") (pintype "passive"))
      (node (ref "R20") (pin "P$2") (pinfunction "2_P$2") (pintype "passive"))
    )
    (net (code "80") (name "Net-(Q8-B)") (class "Default")
      (node (ref "Q8") (pin "2") (pinfunction "B_2") (pintype "passive"))
      (node (ref "R24") (pin "P$2") (pinfunction "2_P$2") (pintype "passive"))
    )
    (net (code "81") (name "Net-(Q8-C)") (class "Default")
      (node (ref "Q8") (pin "3") (pinfunction "C_3") (pintype "passive"))
      (node (ref "R23") (pin "P$2") (pinfunction "2_P$2") (pintype "passive"))
    )
    (net (code "82") (name "Net-(Q9-B)") (class "Default")
      (node (ref "Q9") (pin "2") (pinfunction "B_2") (pintype "passive"))
      (node (ref "R27") (pin "P$2") (pinfunction "2_P$2") (pintype "passive"))
    )
    (net (code "83") (name "Net-(Q9-C)") (class "Default")
      (node (ref "Q9") (pin "3") (pinfunction "C_3") (pintype "passive"))
      (node (ref "R26") (pin "P$2") (pinfunction "2_P$2") (pintype "passive"))
    )
    (net (code "84") (name "Net-(Q10-B)") (class "Default")
      (node (ref "Q10") (pin "2") (pinfunction "B_2") (pintype "passive"))
      (node (ref "R30") (pin "P$2") (pinfunction "2_P$2") (pintype "passive"))
    )
    (net (code "85") (name "Net-(Q10-C)") (class "Default")
      (node (ref "Q10") (pin "3") (pinfunction "C_3") (pintype "passive"))
      (node (ref "R29") (pin "P$2") (pinfunction "2_P$2") (pintype "passive"))
    )
    (net (code "86") (name "Net-(Q11-B)") (class "Default")
      (node (ref "Q11") (pin "2") (pinfunction "B_2") (pintype "passive"))
      (node (ref "R33") (pin "P$2") (pinfunction "2_P$2") (pintype "passive"))
    )
    (net (code "87") (name "Net-(Q11-C)") (class "Default")
      (node (ref "Q11") (pin "3") (pinfunction "C_3") (pintype "passive"))
      (node (ref "R32") (pin "P$2") (pinfunction "2_P$2") (pintype "passive"))
    )
    (net (code "88") (name "Net-(Q12-B)") (class "Default")
      (node (ref "Q12") (pin "2") (pinfunction "B_2") (pintype "passive"))
      (node (ref "R36") (pin "P$2") (pinfunction "2_P$2") (pintype "passive"))
    )
    (net (code "89") (name "Net-(Q12-C)") (class "Default")
      (node (ref "Q12") (pin "3") (pinfunction "C_3") (pintype "passive"))
      (node (ref "R35") (pin "P$2") (pinfunction "2_P$2") (pintype "passive"))
    )
    (net (code "90") (name "Net-(R1-1)") (class "Default")
      (node (ref "JP13") (pin "1") (pinfunction "1_1") (pintype "passive"))
      (node (ref "R1") (pin "P$1") (pinfunction "1_P$1") (pintype "passive"))
    )
    (net (code "91") (name "Net-(R5-1)") (class "Default")
      (node (ref "JP14") (pin "1") (pinfunction "1_1") (pintype "passive"))
      (node (ref "R5") (pin "P$1") (pinfunction "1_P$1") (pintype "passive"))
    )
    (net (code "92") (name "Net-(R8-1)") (class "Default")
      (node (ref "JP16") (pin "1") (pinfunction "1_1") (pintype "passive"))
      (node (ref "R8") (pin "P$1") (pinfunction "1_P$1") (pintype "passive"))
    )
    (net (code "93") (name "Net-(R11-1)") (class "Default")
      (node (ref "JP17") (pin "1") (pinfunction "1_1") (pintype "passive"))
      (node (ref "R11") (pin "P$1") (pinfunction "1_P$1") (pintype "passive"))
    )
    (net (code "94") (name "Net-(R14-1)") (class "Default")
      (node (ref "JP15") (pin "1") (pinfunction "1_1") (pintype "passive"))
      (node (ref "R14") (pin "P$1") (pinfunction "1_P$1") (pintype "passive"))
    )
    (net (code "95") (name "Net-(R17-1)") (class "Default")
      (node (ref "JP18") (pin "1") (pinfunction "1_1") (pintype "passive"))
      (node (ref "R17") (pin "P$1") (pinfunction "1_P$1") (pintype "passive"))
    )
    (net (code "96") (name "Net-(R20-1)") (class "Default")
      (node (ref "JP19") (pin "1") (pinfunction "1_1") (pintype "passive"))
      (node (ref "R20") (pin "P$1") (pinfunction "1_P$1") (pintype "passive"))
    )
    (net (code "97") (name "Net-(R23-1)") (class "Default")
      (node (ref "JP20") (pin "1") (pinfunction "1_1") (pintype "passive"))
      (node (ref "R23") (pin "P$1") (pinfunction "1_P$1") (pintype "passive"))
    )
    (net (code "98") (name "Net-(R26-1)") (class "Default")
      (node (ref "JP21") (pin "1") (pinfunction "1_1") (pintype "passive"))
      (node (ref "R26") (pin "P$1") (pinfunction "1_P$1") (pintype "passive"))
    )
    (net (code "99") (name "Net-(R29-1)") (class "Default")
      (node (ref "JP22") (pin "1") (pinfunction "1_1") (pintype "passive"))
      (node (ref "R29") (pin "P$1") (pinfunction "1_P$1") (pintype "passive"))
    )
    (net (code "100") (name "Net-(R32-1)") (class "Default")
      (node (ref "JP23") (pin "1") (pinfunction "1_1") (pintype "passive"))
      (node (ref "R32") (pin "P$1") (pinfunction "1_P$1") (pintype "passive"))
    )
    (net (code "101") (name "Net-(R35-1)") (class "Default")
      (node (ref "JP24") (pin "1") (pinfunction "1_1") (pintype "passive"))
      (node (ref "R35") (pin "P$1") (pinfunction "1_P$1") (pintype "passive"))
    )
    (net (code "102") (name "RES") (class "Default")
      (node (ref "JP10") (pin "1") (pinfunction "1_1") (pintype "passive"))
    )
    (net (code "103") (name "RX0") (class "Default")
      (node (ref "JP4") (pin "1") (pinfunction "1_1") (pintype "passive"))
    )
    (net (code "104") (name "SCL") (class "Default")
      (node (ref "JP5") (pin "1") (pinfunction "1_1") (pintype "passive"))
    )
    (net (code "105") (name "SCLK") (class "Default")
      (node (ref "JP26") (pin "3") (pinfunction "3_3") (pintype "passive"))
      (node (ref "JP9") (pin "16") (pinfunction "16_16") (pintype "passive"))
    )
    (net (code "106") (name "SDA") (class "Default")
      (node (ref "JP5") (pin "2") (pinfunction "2_2") (pintype "passive"))
    )
    (net (code "107") (name "SD_CS") (class "Default")
      (node (ref "JP26") (pin "4") (pinfunction "4_4") (pintype "passive"))
      (node (ref "JP8") (pin "1") (pinfunction "1_1") (pintype "passive"))
    )
    (net (code "108") (name "SIG-") (class "Default")
      (node (ref "JP25") (pin "2") (pinfunction "2_2") (pintype "passive"))
      (node (ref "JP27") (pin "3") (pinfunction "3_3") (pintype "passive"))
    )
    (net (code "109") (name "SIG-L") (class "Default")
      (node (ref "JP25") (pin "3") (pinfunction "3_3") (pintype "passive"))
      (node (ref "JP27") (pin "2") (pinfunction "2_2") (pintype "passive"))
    )
    (net (code "110") (name "SIG-R") (class "Default")
      (node (ref "JP25") (pin "1") (pinfunction "1_1") (pintype "passive"))
      (node (ref "JP27") (pin "1") (pinfunction "1_1") (pintype "passive"))
    )
    (net (code "111") (name "TX1") (class "Default")
      (node (ref "JP4") (pin "2") (pinfunction "2_2") (pintype "passive"))
    )
    (net (code "112") (name "VIN") (class "Default")
      (node (ref "JP10") (pin "6") (pinfunction "6_6") (pintype "passive"))
      (node (ref "JP25") (pin "5") (pinfunction "5_5") (pintype "passive"))
    )
    (net (code "113") (name "unconnected-(JP3-Pad1)") (class "Default")
      (node (ref "JP3") (pin "1") (pinfunction "1_1") (pintype "passive"))
    )
    (net (code "114") (name "unconnected-(JP3-Pad6)") (class "Default")
      (node (ref "JP3") (pin "6") (pinfunction "6_6") (pintype "passive"))
    )
    (net (code "115") (name "unconnected-(JP4-Pad3)") (class "Default")
      (node (ref "JP4") (pin "3") (pinfunction "3_3") (pintype "passive"))
    )
    (net (code "116") (name "unconnected-(JP4-Pad7)") (class "Default")
      (node (ref "JP4") (pin "7") (pinfunction "7_7") (pintype "passive"))
    )
    (net (code "117") (name "unconnected-(JP4-Pad8)") (class "Default")
      (node (ref "JP4") (pin "8") (pinfunction "8_8") (pintype "passive"))
    )
    (net (code "118") (name "unconnected-(JP25-Pad4)") (class "Default")
      (node (ref "JP25") (pin "4") (pinfunction "4_4") (pintype "passive"))
    )
    (net (code "119") (name "unconnected-(JP25-Pad7)") (class "Default")
      (node (ref "JP25") (pin "7") (pinfunction "7_7") (pintype "passive"))
    )
    (net (code "120") (name "unconnected-(JP25-Pad8)") (class "Default")
      (node (ref "JP25") (pin "8") (pinfunction "8_8") (pintype "passive"))
    )
    (net (code "121") (name "unconnected-(JP25-Pad9)") (class "Default")
      (node (ref "JP25") (pin "9") (pinfunction "9_9") (pintype "passive"))
    )
  )
)
